# TwoMegCoCo_MMU_v1_0.net
KiCad netlist of a schematic drawn in EAGLE
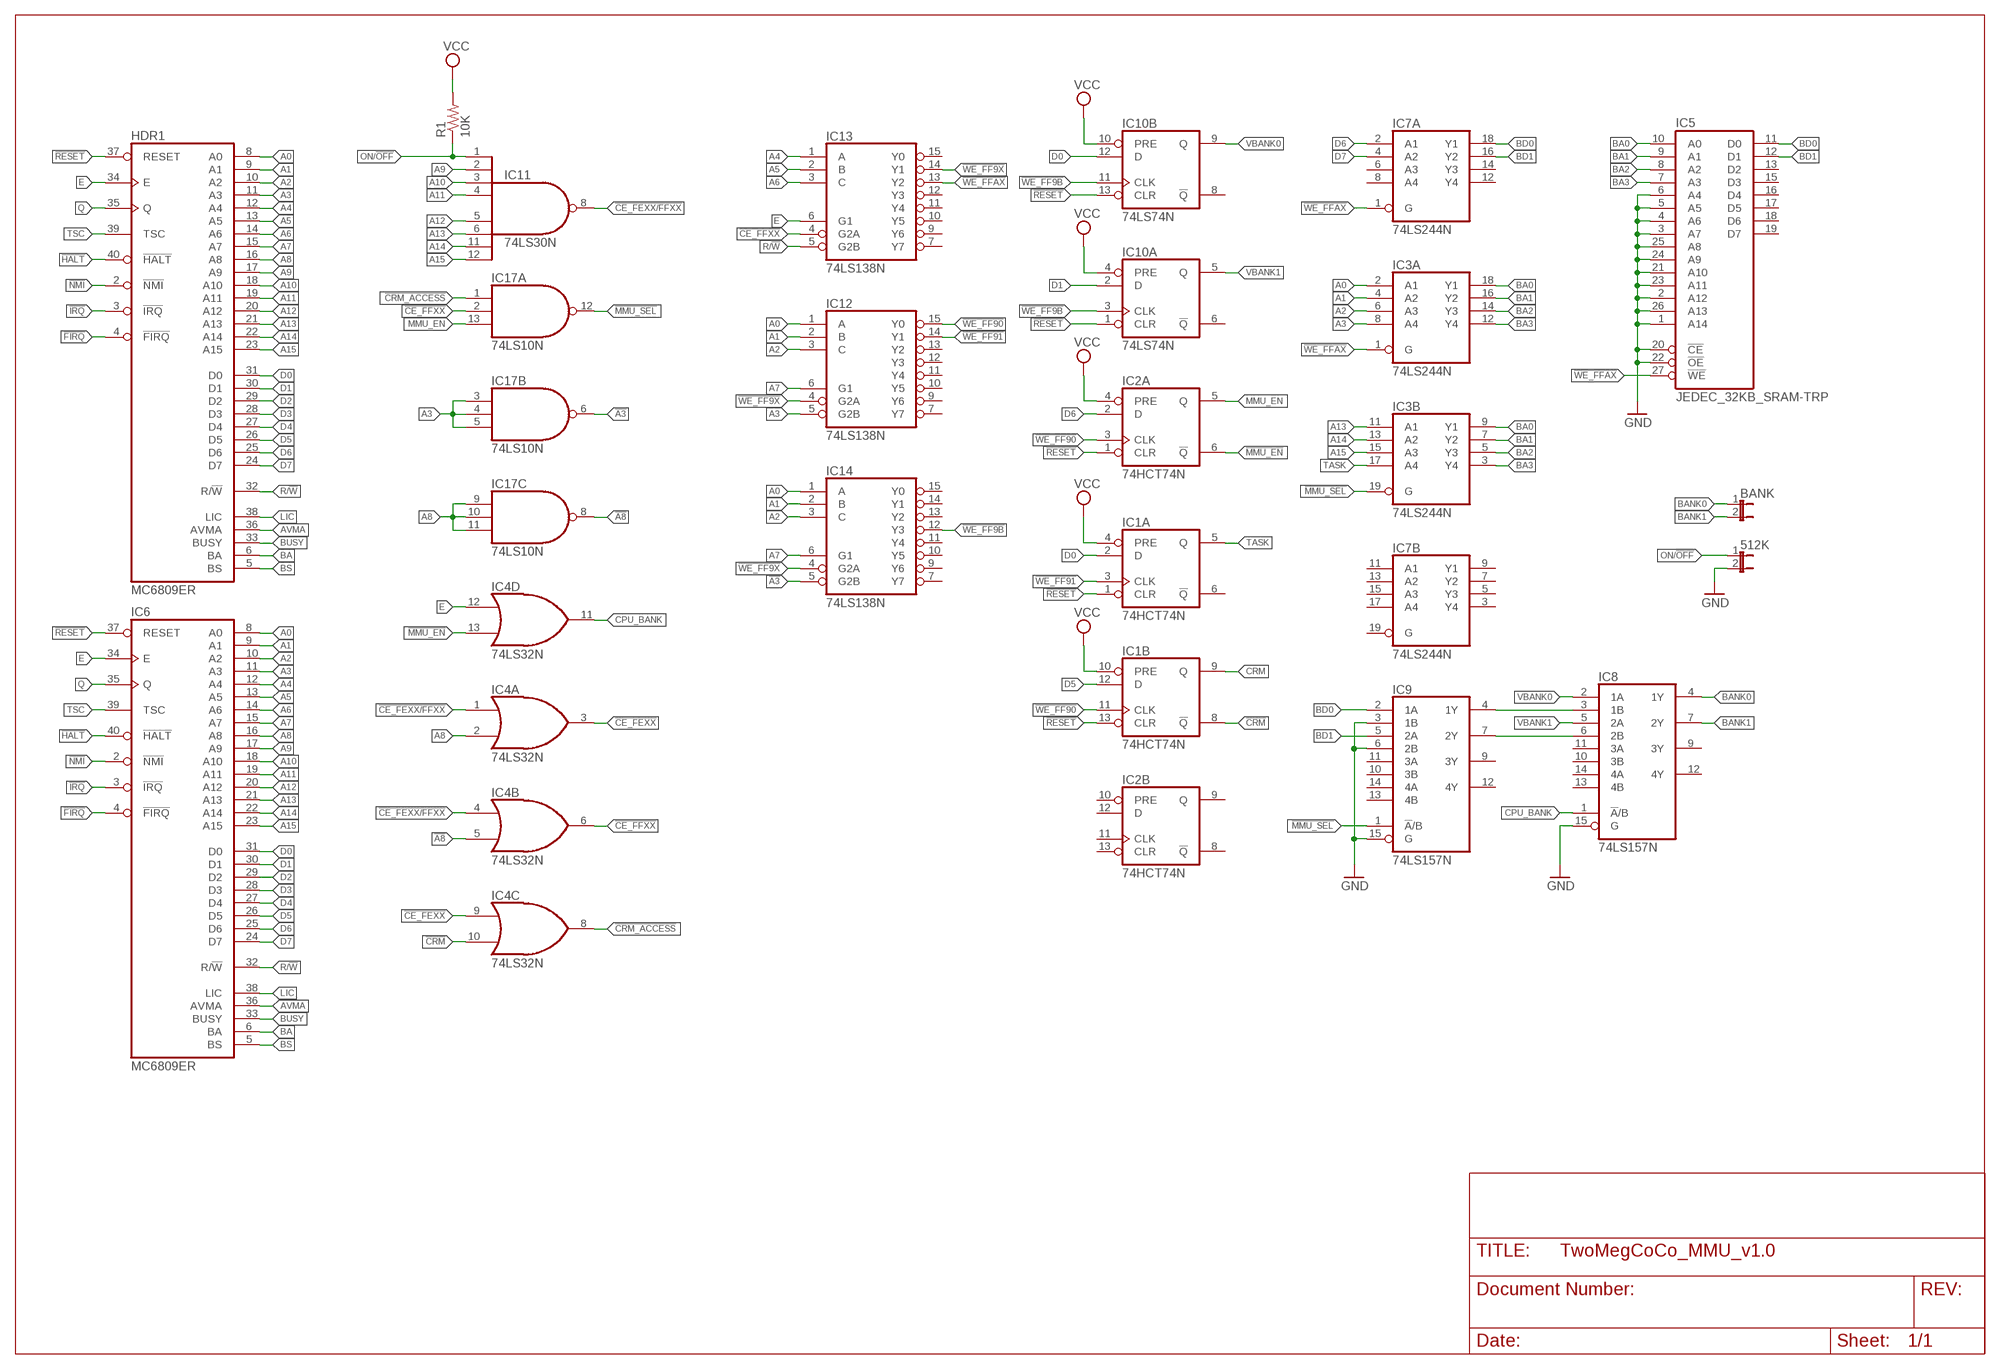
[diagram p0: schematic, sheet 1]

(export (version "E")
  (design (tool "Eeschema 10.0.6"))
  (components
    (comp (ref "512K")
      (value "JP1E")
      (footprint "eagle-import:JP1")
      (libsource (lib "eagle-import") (part "JP1E"))
    )
    (comp (ref "BANK")
      (value "JP1E")
      (footprint "eagle-import:JP1")
      (libsource (lib "eagle-import") (part "JP1E"))
    )
    (comp (ref "HDR1")
      (value "MC6809ER")
      (footprint "eagle-import:DIL40-ROUNDPAD")
      (libsource (lib "eagle-import") (part "MC6809ER"))
    )
    (comp (ref "IC1")
      (value "74HCT74N")
      (footprint "eagle-import:DIL14-RP")
      (libsource (lib "eagle-import") (part "7474NHCT"))
    )
    (comp (ref "IC2")
      (value "74HCT74N")
      (footprint "eagle-import:DIL14-RP")
      (libsource (lib "eagle-import") (part "7474NHCT"))
    )
    (comp (ref "IC3")
      (value "74LS244N")
      (footprint "eagle-import:DIL20-RP")
      (libsource (lib "eagle-import") (part "74244NLS"))
    )
    (comp (ref "IC4")
      (value "74LS32N")
      (footprint "eagle-import:DIL14-RP")
      (libsource (lib "eagle-import") (part "7432NLS"))
    )
    (comp (ref "IC5")
      (value "JEDEC_32KB_SRAM-TRP")
      (footprint "eagle-import:DIL28-3-RP")
      (libsource (lib "eagle-import") (part "JEDEC_32KB_SRAM-TRP"))
    )
    (comp (ref "IC6")
      (value "MC6809ER")
      (footprint "eagle-import:DIL40-ROUNDPAD")
      (libsource (lib "eagle-import") (part "MC6809ER"))
    )
    (comp (ref "IC7")
      (value "74LS244N")
      (footprint "eagle-import:DIL20-RP")
      (libsource (lib "eagle-import") (part "74244NLS"))
    )
    (comp (ref "IC8")
      (value "74LS157N")
      (footprint "eagle-import:DIL16-RP")
      (libsource (lib "eagle-import") (part "74157NLS"))
    )
    (comp (ref "IC9")
      (value "74LS157N")
      (footprint "eagle-import:DIL16-RP")
      (libsource (lib "eagle-import") (part "74157NLS"))
    )
    (comp (ref "IC10")
      (value "74LS74N")
      (footprint "eagle-import:DIL14-RP")
      (libsource (lib "eagle-import") (part "7474NLS"))
    )
    (comp (ref "IC11")
      (value "74LS30N")
      (footprint "eagle-import:DIL14-RP")
      (libsource (lib "eagle-import") (part "7430NLS"))
    )
    (comp (ref "IC12")
      (value "74LS138N")
      (footprint "eagle-import:DIL16-RP")
      (libsource (lib "eagle-import") (part "74138NLS"))
    )
    (comp (ref "IC13")
      (value "74LS138N")
      (footprint "eagle-import:DIL16-RP")
      (libsource (lib "eagle-import") (part "74138NLS"))
    )
    (comp (ref "IC14")
      (value "74LS138N")
      (footprint "eagle-import:DIL16-RP")
      (libsource (lib "eagle-import") (part "74138NLS"))
    )
    (comp (ref "IC17")
      (value "74LS10N")
      (footprint "eagle-import:DIL14-RP")
      (libsource (lib "eagle-import") (part "7410NLS"))
    )
    (comp (ref "R1")
      (value "10K")
      (footprint "eagle-import:0204_7")
      (libsource (lib "eagle-import") (part "R-US_0204/7"))
    )
  )
  (nets
    (net (code "1") (name "/ON{slash}~{OFF}") (class "Default")
      (node (ref "512K") (pin "1") (pinfunction "1_1") (pintype "passive"))
      (node (ref "IC11") (pin "1") (pinfunction "I0_1") (pintype "input"))
      (node (ref "R1") (pin "1") (pinfunction "1_1") (pintype "passive"))
    )
    (net (code "2") (name "/R{slash}~{W}") (class "Default")
      (node (ref "HDR1") (pin "32") (pinfunction "R/~{W}_32") (pintype "output"))
      (node (ref "IC13") (pin "5") (pinfunction "G2B_5") (pintype "input"))
      (node (ref "IC6") (pin "32") (pinfunction "R/~{W}_32") (pintype "output"))
    )
    (net (code "3") (name "/~{A3}") (class "Default")
      (node (ref "IC14") (pin "5") (pinfunction "G2B_5") (pintype "input"))
      (node (ref "IC17") (pin "6") (pinfunction "O_6") (pintype "output"))
    )
    (net (code "4") (name "/~{A8}") (class "Default")
      (node (ref "IC17") (pin "8") (pinfunction "O_8") (pintype "output"))
      (node (ref "IC4") (pin "5") (pinfunction "I1_5") (pintype "input"))
    )
    (net (code "5") (name "/~{CE_FEXX{slash}FFXX}") (class "Default")
      (node (ref "IC11") (pin "8") (pinfunction "O_8") (pintype "output"))
      (node (ref "IC4") (pin "1") (pinfunction "I0_1") (pintype "input"))
      (node (ref "IC4") (pin "4") (pinfunction "I0_4") (pintype "input"))
    )
    (net (code "6") (name "/~{CE_FEXX}") (class "Default")
      (node (ref "IC4") (pin "3") (pinfunction "O_3") (pintype "output"))
      (node (ref "IC4") (pin "9") (pinfunction "I0_9") (pintype "input"))
    )
    (net (code "7") (name "/~{CE_FFXX}") (class "Default")
      (node (ref "IC13") (pin "4") (pinfunction "G2A_4") (pintype "input"))
      (node (ref "IC17") (pin "2") (pinfunction "I1_2") (pintype "input"))
      (node (ref "IC4") (pin "6") (pinfunction "O_6") (pintype "output"))
    )
    (net (code "8") (name "/~{CRM_ACCESS}") (class "Default")
      (node (ref "IC17") (pin "1") (pinfunction "I0_1") (pintype "input"))
      (node (ref "IC4") (pin "8") (pinfunction "O_8") (pintype "output"))
    )
    (net (code "9") (name "/~{CRM}") (class "Default")
      (node (ref "IC1") (pin "8") (pinfunction "~{Q}_8") (pintype "output"))
      (node (ref "IC4") (pin "10") (pinfunction "I1_10") (pintype "input"))
    )
    (net (code "10") (name "/~{FIRQ}") (class "Default")
      (node (ref "HDR1") (pin "4") (pinfunction "~{FIRQ}_4") (pintype "open_collector"))
      (node (ref "IC6") (pin "4") (pinfunction "~{FIRQ}_4") (pintype "open_collector"))
    )
    (net (code "11") (name "/~{HALT}") (class "Default")
      (node (ref "HDR1") (pin "40") (pinfunction "~{HALT}_40") (pintype "open_collector"))
      (node (ref "IC6") (pin "40") (pinfunction "~{HALT}_40") (pintype "open_collector"))
    )
    (net (code "12") (name "/~{IRQ}") (class "Default")
      (node (ref "HDR1") (pin "3") (pinfunction "~{IRQ}_3") (pintype "open_collector"))
      (node (ref "IC6") (pin "3") (pinfunction "~{IRQ}_3") (pintype "open_collector"))
    )
    (net (code "13") (name "/~{MMU_EN}") (class "Default")
      (node (ref "IC2") (pin "6") (pinfunction "~{Q}_6") (pintype "output"))
      (node (ref "IC4") (pin "13") (pinfunction "I1_13") (pintype "input"))
    )
    (net (code "14") (name "/~{MMU_SEL}") (class "Default")
      (node (ref "IC17") (pin "12") (pinfunction "O_12") (pintype "output"))
      (node (ref "IC3") (pin "19") (pinfunction "G_19") (pintype "input"))
      (node (ref "IC9") (pin "1") (pinfunction "~{A}/B_1") (pintype "input"))
    )
    (net (code "15") (name "/~{NMI}") (class "Default")
      (node (ref "HDR1") (pin "2") (pinfunction "~{NMI}_2") (pintype "open_collector"))
      (node (ref "IC6") (pin "2") (pinfunction "~{NMI}_2") (pintype "open_collector"))
    )
    (net (code "16") (name "/~{RESET}") (class "Default")
      (node (ref "HDR1") (pin "37") (pinfunction "RESET_37") (pintype "input"))
      (node (ref "IC1") (pin "1") (pinfunction "CLR_1") (pintype "input"))
      (node (ref "IC1") (pin "13") (pinfunction "CLR_13") (pintype "input"))
      (node (ref "IC10") (pin "1") (pinfunction "CLR_1") (pintype "input"))
      (node (ref "IC10") (pin "13") (pinfunction "CLR_13") (pintype "input"))
      (node (ref "IC2") (pin "1") (pinfunction "CLR_1") (pintype "input"))
      (node (ref "IC6") (pin "37") (pinfunction "RESET_37") (pintype "input"))
    )
    (net (code "17") (name "/~{WE_FF9B}") (class "Default")
      (node (ref "IC10") (pin "11") (pinfunction "CLK_11") (pintype "input"))
      (node (ref "IC10") (pin "3") (pinfunction "CLK_3") (pintype "input"))
      (node (ref "IC14") (pin "12") (pinfunction "Y3_12") (pintype "output"))
    )
    (net (code "18") (name "/~{WE_FF9X}") (class "Default")
      (node (ref "IC12") (pin "4") (pinfunction "G2A_4") (pintype "input"))
      (node (ref "IC13") (pin "14") (pinfunction "Y1_14") (pintype "output"))
      (node (ref "IC14") (pin "4") (pinfunction "G2A_4") (pintype "input"))
    )
    (net (code "19") (name "/~{WE_FF90}") (class "Default")
      (node (ref "IC1") (pin "11") (pinfunction "CLK_11") (pintype "input"))
      (node (ref "IC12") (pin "15") (pinfunction "Y0_15") (pintype "output"))
      (node (ref "IC2") (pin "3") (pinfunction "CLK_3") (pintype "input"))
    )
    (net (code "20") (name "/~{WE_FF91}") (class "Default")
      (node (ref "IC1") (pin "3") (pinfunction "CLK_3") (pintype "input"))
      (node (ref "IC12") (pin "14") (pinfunction "Y1_14") (pintype "output"))
    )
    (net (code "21") (name "/~{WE_FFAX}") (class "Default")
      (node (ref "IC13") (pin "13") (pinfunction "Y2_13") (pintype "output"))
      (node (ref "IC3") (pin "1") (pinfunction "G_1") (pintype "input"))
      (node (ref "IC5") (pin "27") (pinfunction "~{WE}_27") (pintype "input"))
      (node (ref "IC7") (pin "1") (pinfunction "G_1") (pintype "input"))
    )
    (net (code "22") (name "A0") (class "Default")
      (node (ref "HDR1") (pin "8") (pinfunction "A0_8") (pintype "tri_state"))
      (node (ref "IC12") (pin "1") (pinfunction "A_1") (pintype "input"))
      (node (ref "IC14") (pin "1") (pinfunction "A_1") (pintype "input"))
      (node (ref "IC3") (pin "2") (pinfunction "A1_2") (pintype "input"))
      (node (ref "IC6") (pin "8") (pinfunction "A0_8") (pintype "tri_state"))
    )
    (net (code "23") (name "A1") (class "Default")
      (node (ref "HDR1") (pin "9") (pinfunction "A1_9") (pintype "tri_state"))
      (node (ref "IC12") (pin "2") (pinfunction "B_2") (pintype "input"))
      (node (ref "IC14") (pin "2") (pinfunction "B_2") (pintype "input"))
      (node (ref "IC3") (pin "4") (pinfunction "A2_4") (pintype "input"))
      (node (ref "IC6") (pin "9") (pinfunction "A1_9") (pintype "tri_state"))
    )
    (net (code "24") (name "A2") (class "Default")
      (node (ref "HDR1") (pin "10") (pinfunction "A2_10") (pintype "tri_state"))
      (node (ref "IC12") (pin "3") (pinfunction "C_3") (pintype "input"))
      (node (ref "IC14") (pin "3") (pinfunction "C_3") (pintype "input"))
      (node (ref "IC3") (pin "6") (pinfunction "A3_6") (pintype "input"))
      (node (ref "IC6") (pin "10") (pinfunction "A2_10") (pintype "tri_state"))
    )
    (net (code "25") (name "A3") (class "Default")
      (node (ref "HDR1") (pin "11") (pinfunction "A3_11") (pintype "tri_state"))
      (node (ref "IC12") (pin "5") (pinfunction "G2B_5") (pintype "input"))
      (node (ref "IC17") (pin "3") (pinfunction "I0_3") (pintype "input"))
      (node (ref "IC17") (pin "4") (pinfunction "I1_4") (pintype "input"))
      (node (ref "IC17") (pin "5") (pinfunction "I2_5") (pintype "input"))
      (node (ref "IC3") (pin "8") (pinfunction "A4_8") (pintype "input"))
      (node (ref "IC6") (pin "11") (pinfunction "A3_11") (pintype "tri_state"))
    )
    (net (code "26") (name "A4") (class "Default")
      (node (ref "HDR1") (pin "12") (pinfunction "A4_12") (pintype "tri_state"))
      (node (ref "IC13") (pin "1") (pinfunction "A_1") (pintype "input"))
      (node (ref "IC6") (pin "12") (pinfunction "A4_12") (pintype "tri_state"))
    )
    (net (code "27") (name "A5") (class "Default")
      (node (ref "HDR1") (pin "13") (pinfunction "A5_13") (pintype "tri_state"))
      (node (ref "IC13") (pin "2") (pinfunction "B_2") (pintype "input"))
      (node (ref "IC6") (pin "13") (pinfunction "A5_13") (pintype "tri_state"))
    )
    (net (code "28") (name "A6") (class "Default")
      (node (ref "HDR1") (pin "14") (pinfunction "A6_14") (pintype "tri_state"))
      (node (ref "IC13") (pin "3") (pinfunction "C_3") (pintype "input"))
      (node (ref "IC6") (pin "14") (pinfunction "A6_14") (pintype "tri_state"))
    )
    (net (code "29") (name "A7") (class "Default")
      (node (ref "HDR1") (pin "15") (pinfunction "A7_15") (pintype "tri_state"))
      (node (ref "IC12") (pin "6") (pinfunction "G1_6") (pintype "input"))
      (node (ref "IC14") (pin "6") (pinfunction "G1_6") (pintype "input"))
      (node (ref "IC6") (pin "15") (pinfunction "A7_15") (pintype "tri_state"))
    )
    (net (code "30") (name "A8") (class "Default")
      (node (ref "HDR1") (pin "16") (pinfunction "A8_16") (pintype "tri_state"))
      (node (ref "IC17") (pin "10") (pinfunction "I1_10") (pintype "input"))
      (node (ref "IC17") (pin "11") (pinfunction "I2_11") (pintype "input"))
      (node (ref "IC17") (pin "9") (pinfunction "I0_9") (pintype "input"))
      (node (ref "IC4") (pin "2") (pinfunction "I1_2") (pintype "input"))
      (node (ref "IC6") (pin "16") (pinfunction "A8_16") (pintype "tri_state"))
    )
    (net (code "31") (name "A9") (class "Default")
      (node (ref "HDR1") (pin "17") (pinfunction "A9_17") (pintype "tri_state"))
      (node (ref "IC11") (pin "2") (pinfunction "I1_2") (pintype "input"))
      (node (ref "IC6") (pin "17") (pinfunction "A9_17") (pintype "tri_state"))
    )
    (net (code "32") (name "A10") (class "Default")
      (node (ref "HDR1") (pin "18") (pinfunction "A10_18") (pintype "tri_state"))
      (node (ref "IC11") (pin "3") (pinfunction "I2_3") (pintype "input"))
      (node (ref "IC6") (pin "18") (pinfunction "A10_18") (pintype "tri_state"))
    )
    (net (code "33") (name "A11") (class "Default")
      (node (ref "HDR1") (pin "19") (pinfunction "A11_19") (pintype "tri_state"))
      (node (ref "IC11") (pin "4") (pinfunction "I3_4") (pintype "input"))
      (node (ref "IC6") (pin "19") (pinfunction "A11_19") (pintype "tri_state"))
    )
    (net (code "34") (name "A12") (class "Default")
      (node (ref "HDR1") (pin "20") (pinfunction "A12_20") (pintype "tri_state"))
      (node (ref "IC11") (pin "5") (pinfunction "I4_5") (pintype "input"))
      (node (ref "IC6") (pin "20") (pinfunction "A12_20") (pintype "tri_state"))
    )
    (net (code "35") (name "A13") (class "Default")
      (node (ref "HDR1") (pin "21") (pinfunction "A13_21") (pintype "tri_state"))
      (node (ref "IC11") (pin "6") (pinfunction "I5_6") (pintype "input"))
      (node (ref "IC3") (pin "11") (pinfunction "A1_11") (pintype "input"))
      (node (ref "IC6") (pin "21") (pinfunction "A13_21") (pintype "tri_state"))
    )
    (net (code "36") (name "A14") (class "Default")
      (node (ref "HDR1") (pin "22") (pinfunction "A14_22") (pintype "tri_state"))
      (node (ref "IC11") (pin "11") (pinfunction "I6_11") (pintype "input"))
      (node (ref "IC3") (pin "13") (pinfunction "A2_13") (pintype "input"))
      (node (ref "IC6") (pin "22") (pinfunction "A14_22") (pintype "tri_state"))
    )
    (net (code "37") (name "A15") (class "Default")
      (node (ref "HDR1") (pin "23") (pinfunction "A15_23") (pintype "tri_state"))
      (node (ref "IC11") (pin "12") (pinfunction "I7_12") (pintype "input"))
      (node (ref "IC3") (pin "15") (pinfunction "A3_15") (pintype "input"))
      (node (ref "IC6") (pin "23") (pinfunction "A15_23") (pintype "tri_state"))
    )
    (net (code "38") (name "AVMA") (class "Default")
      (node (ref "HDR1") (pin "36") (pinfunction "AVMA_36") (pintype "output"))
      (node (ref "IC6") (pin "36") (pinfunction "AVMA_36") (pintype "output"))
    )
    (net (code "39") (name "BA") (class "Default")
      (node (ref "HDR1") (pin "6") (pinfunction "BA_6") (pintype "output"))
      (node (ref "IC6") (pin "6") (pinfunction "BA_6") (pintype "output"))
    )
    (net (code "40") (name "BA0") (class "Default")
      (node (ref "IC3") (pin "18") (pinfunction "Y1_18") (pintype "tri_state"))
      (node (ref "IC3") (pin "9") (pinfunction "Y1_9") (pintype "tri_state"))
      (node (ref "IC5") (pin "10") (pinfunction "A0_10") (pintype "input"))
    )
    (net (code "41") (name "BA1") (class "Default")
      (node (ref "IC3") (pin "16") (pinfunction "Y2_16") (pintype "tri_state"))
      (node (ref "IC3") (pin "7") (pinfunction "Y2_7") (pintype "tri_state"))
      (node (ref "IC5") (pin "9") (pinfunction "A1_9") (pintype "input"))
    )
    (net (code "42") (name "BA2") (class "Default")
      (node (ref "IC3") (pin "14") (pinfunction "Y3_14") (pintype "tri_state"))
      (node (ref "IC3") (pin "5") (pinfunction "Y3_5") (pintype "tri_state"))
      (node (ref "IC5") (pin "8") (pinfunction "A2_8") (pintype "input"))
    )
    (net (code "43") (name "BA3") (class "Default")
      (node (ref "IC3") (pin "12") (pinfunction "Y4_12") (pintype "tri_state"))
      (node (ref "IC3") (pin "3") (pinfunction "Y4_3") (pintype "tri_state"))
      (node (ref "IC5") (pin "7") (pinfunction "A3_7") (pintype "input"))
    )
    (net (code "44") (name "BANK0") (class "Default")
      (node (ref "BANK") (pin "1") (pinfunction "1_1") (pintype "passive"))
      (node (ref "IC8") (pin "4") (pinfunction "1Y_4") (pintype "output"))
    )
    (net (code "45") (name "BANK1") (class "Default")
      (node (ref "BANK") (pin "2") (pinfunction "2_2") (pintype "passive"))
      (node (ref "IC8") (pin "7") (pinfunction "2Y_7") (pintype "output"))
    )
    (net (code "46") (name "BD0") (class "Default")
      (node (ref "IC5") (pin "11") (pinfunction "D0_11") (pintype "bidirectional"))
      (node (ref "IC7") (pin "18") (pinfunction "Y1_18") (pintype "tri_state"))
      (node (ref "IC9") (pin "2") (pinfunction "1A_2") (pintype "input"))
    )
    (net (code "47") (name "BD1") (class "Default")
      (node (ref "IC5") (pin "12") (pinfunction "D1_12") (pintype "bidirectional"))
      (node (ref "IC7") (pin "16") (pinfunction "Y2_16") (pintype "tri_state"))
      (node (ref "IC9") (pin "5") (pinfunction "2A_5") (pintype "input"))
    )
    (net (code "48") (name "BS") (class "Default")
      (node (ref "HDR1") (pin "5") (pinfunction "BS_5") (pintype "output"))
      (node (ref "IC6") (pin "5") (pinfunction "BS_5") (pintype "output"))
    )
    (net (code "49") (name "BUSY") (class "Default")
      (node (ref "HDR1") (pin "33") (pinfunction "BUSY_33") (pintype "output"))
      (node (ref "IC6") (pin "33") (pinfunction "BUSY_33") (pintype "output"))
    )
    (net (code "50") (name "CPU_BANK") (class "Default")
      (node (ref "IC4") (pin "11") (pinfunction "O_11") (pintype "output"))
      (node (ref "IC8") (pin "1") (pinfunction "~{A}/B_1") (pintype "input"))
    )
    (net (code "51") (name "CRM") (class "Default")
      (node (ref "IC1") (pin "9") (pinfunction "Q_9") (pintype "output"))
    )
    (net (code "52") (name "D0") (class "Default")
      (node (ref "HDR1") (pin "31") (pinfunction "D0_31") (pintype "bidirectional"))
      (node (ref "IC1") (pin "2") (pinfunction "D_2") (pintype "input"))
      (node (ref "IC10") (pin "12") (pinfunction "D_12") (pintype "input"))
      (node (ref "IC6") (pin "31") (pinfunction "D0_31") (pintype "bidirectional"))
    )
    (net (code "53") (name "D1") (class "Default")
      (node (ref "HDR1") (pin "30") (pinfunction "D1_30") (pintype "bidirectional"))
      (node (ref "IC10") (pin "2") (pinfunction "D_2") (pintype "input"))
      (node (ref "IC6") (pin "30") (pinfunction "D1_30") (pintype "bidirectional"))
    )
    (net (code "54") (name "D2") (class "Default")
      (node (ref "HDR1") (pin "29") (pinfunction "D2_29") (pintype "bidirectional"))
      (node (ref "IC6") (pin "29") (pinfunction "D2_29") (pintype "bidirectional"))
    )
    (net (code "55") (name "D3") (class "Default")
      (node (ref "HDR1") (pin "28") (pinfunction "D3_28") (pintype "bidirectional"))
      (node (ref "IC6") (pin "28") (pinfunction "D3_28") (pintype "bidirectional"))
    )
    (net (code "56") (name "D4") (class "Default")
      (node (ref "HDR1") (pin "27") (pinfunction "D4_27") (pintype "bidirectional"))
      (node (ref "IC6") (pin "27") (pinfunction "D4_27") (pintype "bidirectional"))
    )
    (net (code "57") (name "D5") (class "Default")
      (node (ref "HDR1") (pin "26") (pinfunction "D5_26") (pintype "bidirectional"))
      (node (ref "IC1") (pin "12") (pinfunction "D_12") (pintype "input"))
      (node (ref "IC6") (pin "26") (pinfunction "D5_26") (pintype "bidirectional"))
    )
    (net (code "58") (name "D6") (class "Default")
      (node (ref "HDR1") (pin "25") (pinfunction "D6_25") (pintype "bidirectional"))
      (node (ref "IC2") (pin "2") (pinfunction "D_2") (pintype "input"))
      (node (ref "IC6") (pin "25") (pinfunction "D6_25") (pintype "bidirectional"))
      (node (ref "IC7") (pin "2") (pinfunction "A1_2") (pintype "input"))
    )
    (net (code "59") (name "D7") (class "Default")
      (node (ref "HDR1") (pin "24") (pinfunction "D7_24") (pintype "bidirectional"))
      (node (ref "IC6") (pin "24") (pinfunction "D7_24") (pintype "bidirectional"))
      (node (ref "IC7") (pin "4") (pinfunction "A2_4") (pintype "input"))
    )
    (net (code "60") (name "E") (class "Default")
      (node (ref "HDR1") (pin "34") (pinfunction "E_34") (pintype "input"))
      (node (ref "IC13") (pin "6") (pinfunction "G1_6") (pintype "input"))
      (node (ref "IC4") (pin "12") (pinfunction "I0_12") (pintype "input"))
      (node (ref "IC6") (pin "34") (pinfunction "E_34") (pintype "input"))
    )
    (net (code "61") (name "GND") (class "Default")
      (node (ref "512K") (pin "2") (pinfunction "2_2") (pintype "passive"))
      (node (ref "IC5") (pin "1") (pinfunction "A14_1") (pintype "input"))
      (node (ref "IC5") (pin "2") (pinfunction "A12_2") (pintype "input"))
      (node (ref "IC5") (pin "20") (pinfunction "~{CE}_20") (pintype "input"))
      (node (ref "IC5") (pin "21") (pinfunction "A10_21") (pintype "input"))
      (node (ref "IC5") (pin "22") (pinfunction "~{OE}_22") (pintype "input"))
      (node (ref "IC5") (pin "23") (pinfunction "A11_23") (pintype "input"))
      (node (ref "IC5") (pin "24") (pinfunction "A9_24") (pintype "input"))
      (node (ref "IC5") (pin "25") (pinfunction "A8_25") (pintype "input"))
      (node (ref "IC5") (pin "26") (pinfunction "A13_26") (pintype "input"))
      (node (ref "IC5") (pin "3") (pinfunction "A7_3") (pintype "input"))
      (node (ref "IC5") (pin "4") (pinfunction "A6_4") (pintype "input"))
      (node (ref "IC5") (pin "5") (pinfunction "A5_5") (pintype "input"))
      (node (ref "IC5") (pin "6") (pinfunction "A4_6") (pintype "input"))
      (node (ref "IC8") (pin "15") (pinfunction "G_15") (pintype "input"))
      (node (ref "IC9") (pin "15") (pinfunction "G_15") (pintype "input"))
      (node (ref "IC9") (pin "3") (pinfunction "1B_3") (pintype "input"))
      (node (ref "IC9") (pin "6") (pinfunction "2B_6") (pintype "input"))
    )
    (net (code "62") (name "LIC") (class "Default")
      (node (ref "HDR1") (pin "38") (pinfunction "LIC_38") (pintype "output"))
      (node (ref "IC6") (pin "38") (pinfunction "LIC_38") (pintype "output"))
    )
    (net (code "63") (name "MMU_EN") (class "Default")
      (node (ref "IC17") (pin "13") (pinfunction "I2_13") (pintype "input"))
      (node (ref "IC2") (pin "5") (pinfunction "Q_5") (pintype "output"))
    )
    (net (code "64") (name "Net-(IC8A-1B)") (class "Default")
      (node (ref "IC8") (pin "3") (pinfunction "1B_3") (pintype "input"))
      (node (ref "IC9") (pin "4") (pinfunction "1Y_4") (pintype "output"))
    )
    (net (code "65") (name "Net-(IC8A-2B)") (class "Default")
      (node (ref "IC8") (pin "6") (pinfunction "2B_6") (pintype "input"))
      (node (ref "IC9") (pin "7") (pinfunction "2Y_7") (pintype "output"))
    )
    (net (code "66") (name "Q") (class "Default")
      (node (ref "HDR1") (pin "35") (pinfunction "Q_35") (pintype "input"))
      (node (ref "IC6") (pin "35") (pinfunction "Q_35") (pintype "input"))
    )
    (net (code "67") (name "TASK") (class "Default")
      (node (ref "IC1") (pin "5") (pinfunction "Q_5") (pintype "output"))
      (node (ref "IC3") (pin "17") (pinfunction "A4_17") (pintype "input"))
    )
    (net (code "68") (name "TSC") (class "Default")
      (node (ref "HDR1") (pin "39") (pinfunction "TSC_39") (pintype "open_collector"))
      (node (ref "IC6") (pin "39") (pinfunction "TSC_39") (pintype "open_collector"))
    )
    (net (code "69") (name "VBANK0") (class "Default")
      (node (ref "IC10") (pin "9") (pinfunction "Q_9") (pintype "output"))
      (node (ref "IC8") (pin "2") (pinfunction "1A_2") (pintype "input"))
    )
    (net (code "70") (name "VBANK1") (class "Default")
      (node (ref "IC10") (pin "5") (pinfunction "Q_5") (pintype "output"))
      (node (ref "IC8") (pin "5") (pinfunction "2A_5") (pintype "input"))
    )
    (net (code "71") (name "VCC") (class "Default")
      (node (ref "IC1") (pin "10") (pinfunction "PRE_10") (pintype "input"))
      (node (ref "IC1") (pin "4") (pinfunction "PRE_4") (pintype "input"))
      (node (ref "IC10") (pin "10") (pinfunction "PRE_10") (pintype "input"))
      (node (ref "IC10") (pin "4") (pinfunction "PRE_4") (pintype "input"))
      (node (ref "IC2") (pin "4") (pinfunction "PRE_4") (pintype "input"))
      (node (ref "R1") (pin "2") (pinfunction "2_2") (pintype "passive"))
    )
    (net (code "72") (name "unconnected-(IC1A-~{Q}-Pad6)") (class "Default")
      (node (ref "IC1") (pin "6") (pinfunction "~{Q}_6") (pintype "output"))
    )
    (net (code "73") (name "unconnected-(IC2B-CLK-Pad11)") (class "Default")
      (node (ref "IC2") (pin "11") (pinfunction "CLK_11") (pintype "input"))
    )
    (net (code "74") (name "unconnected-(IC2B-CLR-Pad13)") (class "Default")
      (node (ref "IC2") (pin "13") (pinfunction "CLR_13") (pintype "input"))
    )
    (net (code "75") (name "unconnected-(IC2B-D-Pad12)") (class "Default")
      (node (ref "IC2") (pin "12") (pinfunction "D_12") (pintype "input"))
    )
    (net (code "76") (name "unconnected-(IC2B-PRE-Pad10)") (class "Default")
      (node (ref "IC2") (pin "10") (pinfunction "PRE_10") (pintype "input"))
    )
    (net (code "77") (name "unconnected-(IC2B-Q-Pad9)") (class "Default")
      (node (ref "IC2") (pin "9") (pinfunction "Q_9") (pintype "output"))
    )
    (net (code "78") (name "unconnected-(IC2B-~{Q}-Pad8)") (class "Default")
      (node (ref "IC2") (pin "8") (pinfunction "~{Q}_8") (pintype "output"))
    )
    (net (code "79") (name "unconnected-(IC5A-D2-Pad13)") (class "Default")
      (node (ref "IC5") (pin "13") (pinfunction "D2_13") (pintype "bidirectional"))
    )
    (net (code "80") (name "unconnected-(IC5A-D3-Pad15)") (class "Default")
      (node (ref "IC5") (pin "15") (pinfunction "D3_15") (pintype "bidirectional"))
    )
    (net (code "81") (name "unconnected-(IC5A-D4-Pad16)") (class "Default")
      (node (ref "IC5") (pin "16") (pinfunction "D4_16") (pintype "bidirectional"))
    )
    (net (code "82") (name "unconnected-(IC5A-D5-Pad17)") (class "Default")
      (node (ref "IC5") (pin "17") (pinfunction "D5_17") (pintype "bidirectional"))
    )
    (net (code "83") (name "unconnected-(IC5A-D6-Pad18)") (class "Default")
      (node (ref "IC5") (pin "18") (pinfunction "D6_18") (pintype "bidirectional"))
    )
    (net (code "84") (name "unconnected-(IC5A-D7-Pad19)") (class "Default")
      (node (ref "IC5") (pin "19") (pinfunction "D7_19") (pintype "bidirectional"))
    )
    (net (code "85") (name "unconnected-(IC7A-A3-Pad6)") (class "Default")
      (node (ref "IC7") (pin "6") (pinfunction "A3_6") (pintype "input"))
    )
    (net (code "86") (name "unconnected-(IC7A-A4-Pad8)") (class "Default")
      (node (ref "IC7") (pin "8") (pinfunction "A4_8") (pintype "input"))
    )
    (net (code "87") (name "unconnected-(IC7A-Y3-Pad14)") (class "Default")
      (node (ref "IC7") (pin "14") (pinfunction "Y3_14") (pintype "tri_state"))
    )
    (net (code "88") (name "unconnected-(IC7A-Y4-Pad12)") (class "Default")
      (node (ref "IC7") (pin "12") (pinfunction "Y4_12") (pintype "tri_state"))
    )
    (net (code "89") (name "unconnected-(IC7B-A1-Pad11)") (class "Default")
      (node (ref "IC7") (pin "11") (pinfunction "A1_11") (pintype "input"))
    )
    (net (code "90") (name "unconnected-(IC7B-A2-Pad13)") (class "Default")
      (node (ref "IC7") (pin "13") (pinfunction "A2_13") (pintype "input"))
    )
    (net (code "91") (name "unconnected-(IC7B-A3-Pad15)") (class "Default")
      (node (ref "IC7") (pin "15") (pinfunction "A3_15") (pintype "input"))
    )
    (net (code "92") (name "unconnected-(IC7B-A4-Pad17)") (class "Default")
      (node (ref "IC7") (pin "17") (pinfunction "A4_17") (pintype "input"))
    )
    (net (code "93") (name "unconnected-(IC7B-G-Pad19)") (class "Default")
      (node (ref "IC7") (pin "19") (pinfunction "G_19") (pintype "input"))
    )
    (net (code "94") (name "unconnected-(IC7B-Y1-Pad9)") (class "Default")
      (node (ref "IC7") (pin "9") (pinfunction "Y1_9") (pintype "tri_state"))
    )
    (net (code "95") (name "unconnected-(IC7B-Y2-Pad7)") (class "Default")
      (node (ref "IC7") (pin "7") (pinfunction "Y2_7") (pintype "tri_state"))
    )
    (net (code "96") (name "unconnected-(IC7B-Y3-Pad5)") (class "Default")
      (node (ref "IC7") (pin "5") (pinfunction "Y3_5") (pintype "tri_state"))
    )
    (net (code "97") (name "unconnected-(IC7B-Y4-Pad3)") (class "Default")
      (node (ref "IC7") (pin "3") (pinfunction "Y4_3") (pintype "tri_state"))
    )
    (net (code "98") (name "unconnected-(IC8A-3A-Pad11)") (class "Default")
      (node (ref "IC8") (pin "11") (pinfunction "3A_11") (pintype "input"))
    )
    (net (code "99") (name "unconnected-(IC8A-3B-Pad10)") (class "Default")
      (node (ref "IC8") (pin "10") (pinfunction "3B_10") (pintype "input"))
    )
    (net (code "100") (name "unconnected-(IC8A-3Y-Pad9)") (class "Default")
      (node (ref "IC8") (pin "9") (pinfunction "3Y_9") (pintype "output"))
    )
    (net (code "101") (name "unconnected-(IC8A-4A-Pad14)") (class "Default")
      (node (ref "IC8") (pin "14") (pinfunction "4A_14") (pintype "input"))
    )
    (net (code "102") (name "unconnected-(IC8A-4B-Pad13)") (class "Default")
      (node (ref "IC8") (pin "13") (pinfunction "4B_13") (pintype "input"))
    )
    (net (code "103") (name "unconnected-(IC8A-4Y-Pad12)") (class "Default")
      (node (ref "IC8") (pin "12") (pinfunction "4Y_12") (pintype "output"))
    )
    (net (code "104") (name "unconnected-(IC9A-3A-Pad11)") (class "Default")
      (node (ref "IC9") (pin "11") (pinfunction "3A_11") (pintype "input"))
    )
    (net (code "105") (name "unconnected-(IC9A-3B-Pad10)") (class "Default")
      (node (ref "IC9") (pin "10") (pinfunction "3B_10") (pintype "input"))
    )
    (net (code "106") (name "unconnected-(IC9A-3Y-Pad9)") (class "Default")
      (node (ref "IC9") (pin "9") (pinfunction "3Y_9") (pintype "output"))
    )
    (net (code "107") (name "unconnected-(IC9A-4A-Pad14)") (class "Default")
      (node (ref "IC9") (pin "14") (pinfunction "4A_14") (pintype "input"))
    )
    (net (code "108") (name "unconnected-(IC9A-4B-Pad13)") (class "Default")
      (node (ref "IC9") (pin "13") (pinfunction "4B_13") (pintype "input"))
    )
    (net (code "109") (name "unconnected-(IC9A-4Y-Pad12)") (class "Default")
      (node (ref "IC9") (pin "12") (pinfunction "4Y_12") (pintype "output"))
    )
    (net (code "110") (name "unconnected-(IC10A-~{Q}-Pad6)") (class "Default")
      (node (ref "IC10") (pin "6") (pinfunction "~{Q}_6") (pintype "output"))
    )
    (net (code "111") (name "unconnected-(IC10B-~{Q}-Pad8)") (class "Default")
      (node (ref "IC10") (pin "8") (pinfunction "~{Q}_8") (pintype "output"))
    )
    (net (code "112") (name "unconnected-(IC12A-Y2-Pad13)") (class "Default")
      (node (ref "IC12") (pin "13") (pinfunction "Y2_13") (pintype "output"))
    )
    (net (code "113") (name "unconnected-(IC12A-Y3-Pad12)") (class "Default")
      (node (ref "IC12") (pin "12") (pinfunction "Y3_12") (pintype "output"))
    )
    (net (code "114") (name "unconnected-(IC12A-Y4-Pad11)") (class "Default")
      (node (ref "IC12") (pin "11") (pinfunction "Y4_11") (pintype "output"))
    )
    (net (code "115") (name "unconnected-(IC12A-Y5-Pad10)") (class "Default")
      (node (ref "IC12") (pin "10") (pinfunction "Y5_10") (pintype "output"))
    )
    (net (code "116") (name "unconnected-(IC12A-Y6-Pad9)") (class "Default")
      (node (ref "IC12") (pin "9") (pinfunction "Y6_9") (pintype "output"))
    )
    (net (code "117") (name "unconnected-(IC12A-Y7-Pad7)") (class "Default")
      (node (ref "IC12") (pin "7") (pinfunction "Y7_7") (pintype "output"))
    )
    (net (code "118") (name "unconnected-(IC13A-Y0-Pad15)") (class "Default")
      (node (ref "IC13") (pin "15") (pinfunction "Y0_15") (pintype "output"))
    )
    (net (code "119") (name "unconnected-(IC13A-Y3-Pad12)") (class "Default")
      (node (ref "IC13") (pin "12") (pinfunction "Y3_12") (pintype "output"))
    )
    (net (code "120") (name "unconnected-(IC13A-Y4-Pad11)") (class "Default")
      (node (ref "IC13") (pin "11") (pinfunction "Y4_11") (pintype "output"))
    )
    (net (code "121") (name "unconnected-(IC13A-Y5-Pad10)") (class "Default")
      (node (ref "IC13") (pin "10") (pinfunction "Y5_10") (pintype "output"))
    )
    (net (code "122") (name "unconnected-(IC13A-Y6-Pad9)") (class "Default")
      (node (ref "IC13") (pin "9") (pinfunction "Y6_9") (pintype "output"))
    )
    (net (code "123") (name "unconnected-(IC13A-Y7-Pad7)") (class "Default")
      (node (ref "IC13") (pin "7") (pinfunction "Y7_7") (pintype "output"))
    )
    (net (code "124") (name "unconnected-(IC14A-Y0-Pad15)") (class "Default")
      (node (ref "IC14") (pin "15") (pinfunction "Y0_15") (pintype "output"))
    )
    (net (code "125") (name "unconnected-(IC14A-Y1-Pad14)") (class "Default")
      (node (ref "IC14") (pin "14") (pinfunction "Y1_14") (pintype "output"))
    )
    (net (code "126") (name "unconnected-(IC14A-Y2-Pad13)") (class "Default")
      (node (ref "IC14") (pin "13") (pinfunction "Y2_13") (pintype "output"))
    )
    (net (code "127") (name "unconnected-(IC14A-Y4-Pad11)") (class "Default")
      (node (ref "IC14") (pin "11") (pinfunction "Y4_11") (pintype "output"))
    )
    (net (code "128") (name "unconnected-(IC14A-Y5-Pad10)") (class "Default")
      (node (ref "IC14") (pin "10") (pinfunction "Y5_10") (pintype "output"))
    )
    (net (code "129") (name "unconnected-(IC14A-Y6-Pad9)") (class "Default")
      (node (ref "IC14") (pin "9") (pinfunction "Y6_9") (pintype "output"))
    )
    (net (code "130") (name "unconnected-(IC14A-Y7-Pad7)") (class "Default")
      (node (ref "IC14") (pin "7") (pinfunction "Y7_7") (pintype "output"))
    )
  )
)
